# ATtinyRemote.net
KiCad netlist of a schematic drawn in EAGLE
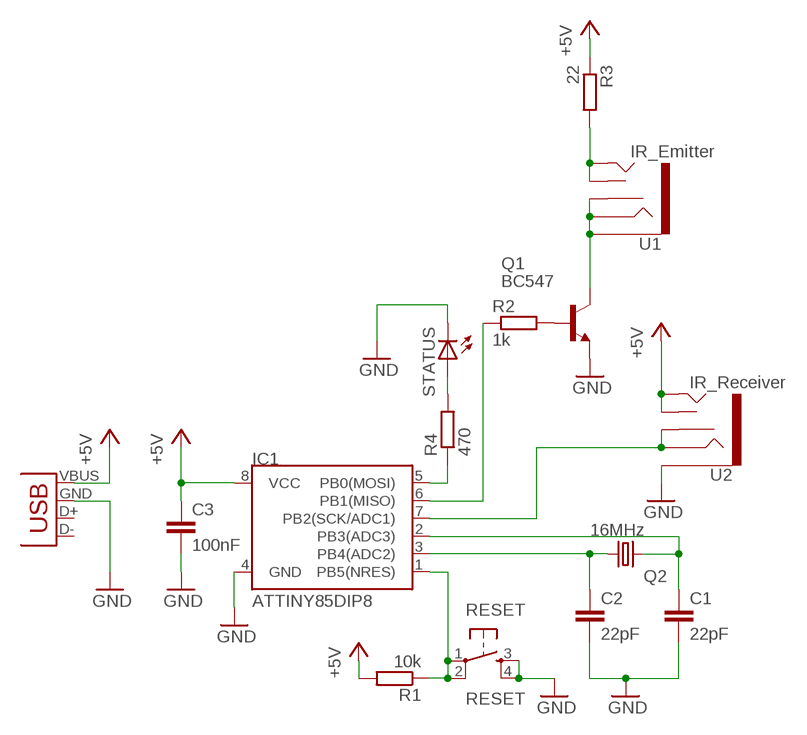
[diagram p0: schematic, sheet 1]

(export (version "E")
  (design (tool "Eeschema 10.0.6"))
  (components
    (comp (ref "C1")
      (value "22pF")
      (footprint "eagle-import:C025-025X050")
      (libsource (lib "eagle-import") (part "C-EU025-025X050"))
    )
    (comp (ref "C2")
      (value "22pF")
      (footprint "eagle-import:C025-025X050")
      (libsource (lib "eagle-import") (part "C-EU025-025X050"))
    )
    (comp (ref "C3")
      (value "100nF")
      (footprint "eagle-import:C025-025X050")
      (libsource (lib "eagle-import") (part "C-EU025-025X050"))
    )
    (comp (ref "IC1")
      (value "ATTINY85DIP8")
      (footprint "eagle-import:DIP08")
      (libsource (lib "eagle-import") (part "ATTINY85DIP8"))
    )
    (comp (ref "Q1")
      (value "BC547")
      (footprint "eagle-import:TO92")
      (libsource (lib "eagle-import") (part "BC547"))
    )
    (comp (ref "Q2")
      (value "16MHz")
      (footprint "eagle-import:HC49_S")
      (libsource (lib "eagle-import") (part "CRYSTALHC49S"))
    )
    (comp (ref "R1")
      (value "10k")
      (footprint "eagle-import:0207_10")
      (libsource (lib "eagle-import") (part "R-EU_0207/10"))
    )
    (comp (ref "R2")
      (value "1k")
      (footprint "eagle-import:0207_10")
      (libsource (lib "eagle-import") (part "R-EU_0207/10"))
    )
    (comp (ref "R3")
      (value "22")
      (footprint "eagle-import:0207_10")
      (libsource (lib "eagle-import") (part "R-EU_0207/10"))
    )
    (comp (ref "R4")
      (value "470")
      (footprint "eagle-import:0207_10")
      (libsource (lib "eagle-import") (part "R-EU_0207/10"))
    )
    (comp (ref "RESET")
      (value "RESET")
      (footprint "eagle-import:TACTILE-PTH")
      (libsource (lib "eagle-import") (part "TAC_SWITCHPTH"))
    )
    (comp (ref "STATUS")
      (value "LED3MM")
      (footprint "eagle-import:LED3MM")
      (libsource (lib "eagle-import") (part "LED3MM"))
    )
    (comp (ref "U1")
      (value "IR_Emitter")
      (footprint "eagle-import:AUDIO-JACK")
      (libsource (lib "eagle-import") (part "AUDIO-JACK2PTH"))
    )
    (comp (ref "U2")
      (value "IR_Receiver")
      (footprint "eagle-import:AUDIO-JACK")
      (libsource (lib "eagle-import") (part "AUDIO-JACK2PTH"))
    )
    (comp (ref "X1")
      (value "USB-A-H")
      (footprint "eagle-import:USB-A-H")
      (libsource (lib "eagle-import") (part "USB-A-H"))
    )
  )
  (nets
    (net (code "1") (name "+5V") (class "Default")
      (node (ref "C3") (pin "1") (pinfunction "1_1") (pintype "passive"))
      (node (ref "IC1") (pin "8") (pinfunction "VCC_8") (pintype "bidirectional"))
      (node (ref "R1") (pin "2") (pinfunction "2_2") (pintype "passive"))
      (node (ref "R3") (pin "1") (pinfunction "1_1") (pintype "passive"))
      (node (ref "U2") (pin "TIP") (pinfunction "TIP_TIP") (pintype "bidirectional"))
      (node (ref "U2") (pin "TSH") (pinfunction "TSH_TSH") (pintype "bidirectional"))
      (node (ref "X1") (pin "VBUS") (pinfunction "GND_VBUS") (pintype "bidirectional"))
    )
    (net (code "2") (name "GND") (class "Default")
      (node (ref "C1") (pin "2") (pinfunction "2_2") (pintype "passive"))
      (node (ref "C2") (pin "2") (pinfunction "2_2") (pintype "passive"))
      (node (ref "C3") (pin "2") (pinfunction "2_2") (pintype "passive"))
      (node (ref "IC1") (pin "4") (pinfunction "GND_4") (pintype "bidirectional"))
      (node (ref "Q1") (pin "1") (pinfunction "E_1") (pintype "passive"))
      (node (ref "RESET") (pin "3") (pinfunction "3_3") (pintype "passive"))
      (node (ref "RESET") (pin "4") (pinfunction "4_4") (pintype "passive"))
      (node (ref "STATUS") (pin "K") (pinfunction "C_K") (pintype "passive"))
      (node (ref "U2") (pin "SLEEVE") (pinfunction "SLEEVE_SLEEVE") (pintype "bidirectional"))
      (node (ref "X1") (pin "GND") (pinfunction "VBUS_GND") (pintype "bidirectional"))
    )
    (net (code "3") (name "Net-(IC1-PB0(MOSI))") (class "Default")
      (node (ref "IC1") (pin "5") (pinfunction "PB0(MOSI)_5") (pintype "bidirectional"))
      (node (ref "R4") (pin "1") (pinfunction "1_1") (pintype "passive"))
    )
    (net (code "4") (name "Net-(IC1-PB1(MISO))") (class "Default")
      (node (ref "IC1") (pin "6") (pinfunction "PB1(MISO)_6") (pintype "bidirectional"))
      (node (ref "R2") (pin "1") (pinfunction "1_1") (pintype "passive"))
    )
    (net (code "5") (name "Net-(IC1-PB2(SCK{slash}ADC1))") (class "Default")
      (node (ref "IC1") (pin "7") (pinfunction "PB2(SCK/ADC1)_7") (pintype "bidirectional"))
      (node (ref "U2") (pin "RING") (pinfunction "RING_RING") (pintype "bidirectional"))
      (node (ref "U2") (pin "RSH") (pinfunction "RSH_RSH") (pintype "bidirectional"))
    )
    (net (code "6") (name "Net-(IC1-PB3(ADC3))") (class "Default")
      (node (ref "C1") (pin "1") (pinfunction "1_1") (pintype "passive"))
      (node (ref "IC1") (pin "2") (pinfunction "PB3(ADC3)_2") (pintype "bidirectional"))
      (node (ref "Q2") (pin "2") (pinfunction "2_2") (pintype "passive"))
    )
    (net (code "7") (name "Net-(IC1-PB4(ADC2))") (class "Default")
      (node (ref "C2") (pin "1") (pinfunction "1_1") (pintype "passive"))
      (node (ref "IC1") (pin "3") (pinfunction "PB4(ADC2)_3") (pintype "bidirectional"))
      (node (ref "Q2") (pin "1") (pinfunction "1_1") (pintype "passive"))
    )
    (net (code "8") (name "Net-(IC1-PB5(NRES))") (class "Default")
      (node (ref "IC1") (pin "1") (pinfunction "PB5(NRES)_1") (pintype "bidirectional"))
      (node (ref "R1") (pin "1") (pinfunction "1_1") (pintype "passive"))
      (node (ref "RESET") (pin "1") (pinfunction "1_1") (pintype "passive"))
      (node (ref "RESET") (pin "2") (pinfunction "2_2") (pintype "passive"))
    )
    (net (code "9") (name "Net-(Q1-B)") (class "Default")
      (node (ref "Q1") (pin "2") (pinfunction "B_2") (pintype "passive"))
      (node (ref "R2") (pin "2") (pinfunction "2_2") (pintype "passive"))
    )
    (net (code "10") (name "Net-(Q1-C)") (class "Default")
      (node (ref "Q1") (pin "3") (pinfunction "C_3") (pintype "passive"))
      (node (ref "U1") (pin "RING") (pinfunction "RING_RING") (pintype "bidirectional"))
      (node (ref "U1") (pin "RSH") (pinfunction "RSH_RSH") (pintype "bidirectional"))
      (node (ref "U1") (pin "SLEEVE") (pinfunction "SLEEVE_SLEEVE") (pintype "bidirectional"))
    )
    (net (code "11") (name "Net-(R3-Pad2)") (class "Default")
      (node (ref "R3") (pin "2") (pinfunction "2_2") (pintype "passive"))
      (node (ref "U1") (pin "TIP") (pinfunction "TIP_TIP") (pintype "bidirectional"))
      (node (ref "U1") (pin "TSH") (pinfunction "TSH_TSH") (pintype "bidirectional"))
    )
    (net (code "12") (name "Net-(R4-Pad2)") (class "Default")
      (node (ref "R4") (pin "2") (pinfunction "2_2") (pintype "passive"))
      (node (ref "STATUS") (pin "A") (pinfunction "A_A") (pintype "passive"))
    )
    (net (code "13") (name "unconnected-(X1-D+-PadD-)") (class "Default")
      (node (ref "X1") (pin "D-") (pinfunction "D+_D-") (pintype "bidirectional"))
    )
    (net (code "14") (name "unconnected-(X1-D--PadD+)") (class "Default")
      (node (ref "X1") (pin "D+") (pinfunction "D-_D+") (pintype "bidirectional"))
    )
  )
)
